# Multiplexed_Row.net
KiCad netlist of a schematic drawn in Altium Designer
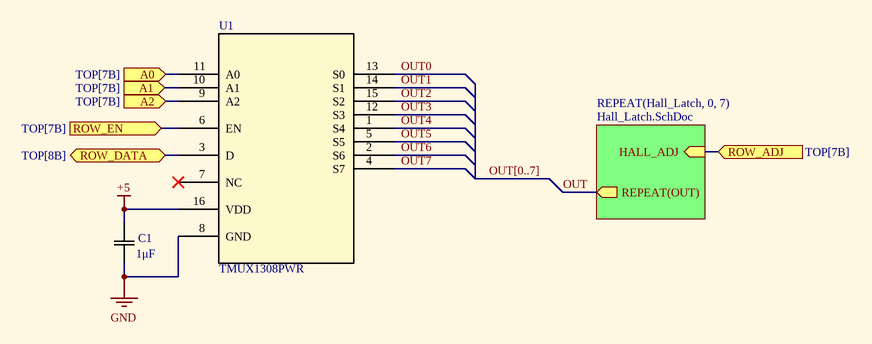
[diagram p0: Multiplexed_Row.SchDoc]

(export (version "E")
  (design (tool "Eeschema 10.0.6"))
  (components
    (comp (ref "C1")
      (value "1μF")
      (footprint "CAP_CL10_SAM")
      (description "No Description Available")
      (libsource (lib "Component_Schematics") (part "CL10B104KB8NNWC"))
    )
    (comp (ref "U1")
      (value "TMUX1308PWR")
      (footprint "TSSOP16_PW_TEX")
      (description "No Description Available")
      (libsource (lib "Component_Schematics") (part "TMUX1308PWR"))
    )
  )
  (nets
    (net (code "1") (name "+5") (class "Default")
      (node (ref "C1") (pin "2") (pinfunction "2_2") (pintype "passive"))
      (node (ref "U1") (pin "16") (pinfunction "VDD_16") (pintype "power_in"))
    )
    (net (code "2") (name "/A0") (class "Default")
      (node (ref "U1") (pin "11") (pinfunction "A0_11") (pintype "passive"))
    )
    (net (code "3") (name "/A1") (class "Default")
      (node (ref "U1") (pin "10") (pinfunction "A1_10") (pintype "passive"))
    )
    (net (code "4") (name "/A2") (class "Default")
      (node (ref "U1") (pin "9") (pinfunction "A2_9") (pintype "passive"))
    )
    (net (code "6") (name "/OUT0") (class "Default")
      (node (ref "U1") (pin "13") (pinfunction "S0_13") (pintype "passive"))
    )
    (net (code "7") (name "/OUT1") (class "Default")
      (node (ref "U1") (pin "14") (pinfunction "S1_14") (pintype "passive"))
    )
    (net (code "8") (name "/OUT2") (class "Default")
      (node (ref "U1") (pin "15") (pinfunction "S2_15") (pintype "passive"))
    )
    (net (code "9") (name "/OUT3") (class "Default")
      (node (ref "U1") (pin "12") (pinfunction "S3_12") (pintype "passive"))
    )
    (net (code "10") (name "/OUT4") (class "Default")
      (node (ref "U1") (pin "1") (pinfunction "S4_1") (pintype "passive"))
    )
    (net (code "11") (name "/OUT5") (class "Default")
      (node (ref "U1") (pin "5") (pinfunction "S5_5") (pintype "passive"))
    )
    (net (code "12") (name "/OUT6") (class "Default")
      (node (ref "U1") (pin "2") (pinfunction "S6_2") (pintype "passive"))
    )
    (net (code "13") (name "/OUT7") (class "Default")
      (node (ref "U1") (pin "4") (pinfunction "S7_4") (pintype "passive"))
    )
    (net (code "16") (name "/ROW_DATA") (class "Default")
      (node (ref "U1") (pin "3") (pinfunction "D_3") (pintype "passive"))
    )
    (net (code "17") (name "/ROW_EN") (class "Default")
      (node (ref "U1") (pin "6") (pinfunction "EN_6") (pintype "passive"))
    )
    (net (code "18") (name "GND") (class "Default")
      (node (ref "C1") (pin "1") (pinfunction "1_1") (pintype "passive"))
      (node (ref "U1") (pin "8") (pinfunction "GND_8") (pintype "power_in"))
    )
    (net (code "19") (name "unconnected-(U1-NC-Pad7)") (class "Default")
      (node (ref "U1") (pin "7") (pinfunction "NC_7") (pintype "passive+no_connect"))
    )
  )
)
